# SCH_ESP-Mar_2024-04-21_1.net
KiCad netlist of a schematic drawn in EasyEDA
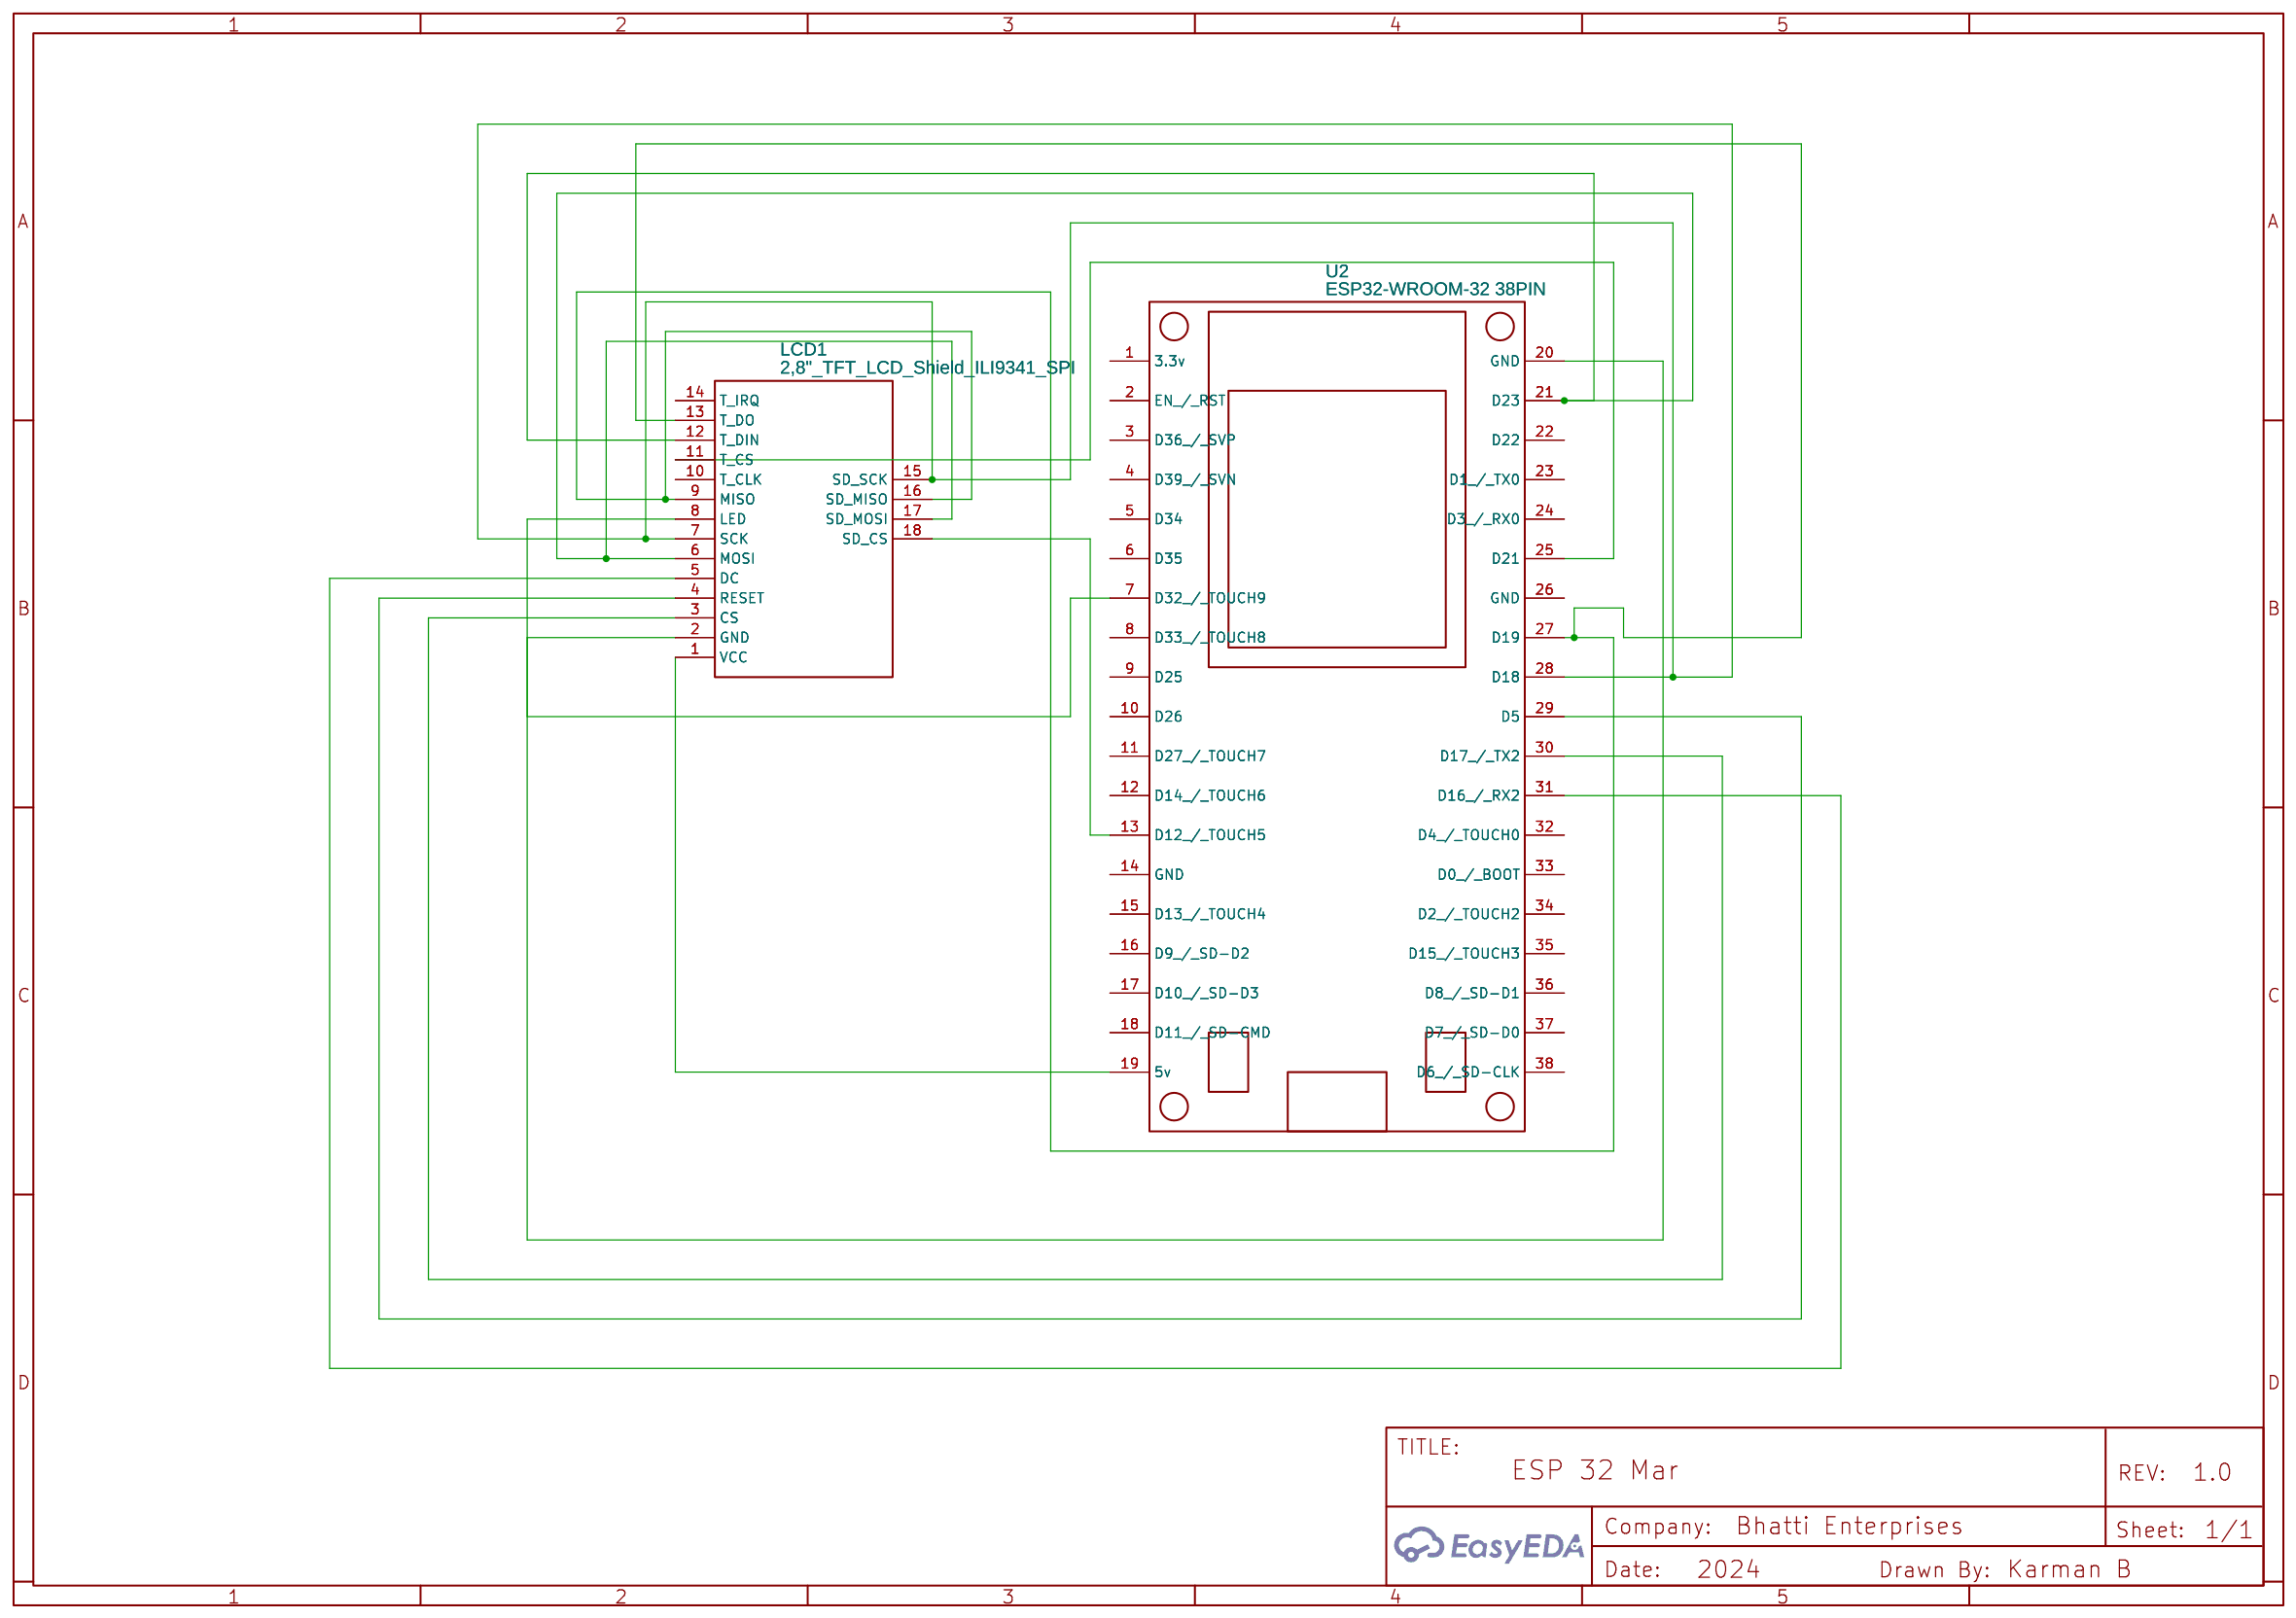
[diagram p0: Sheet_1]
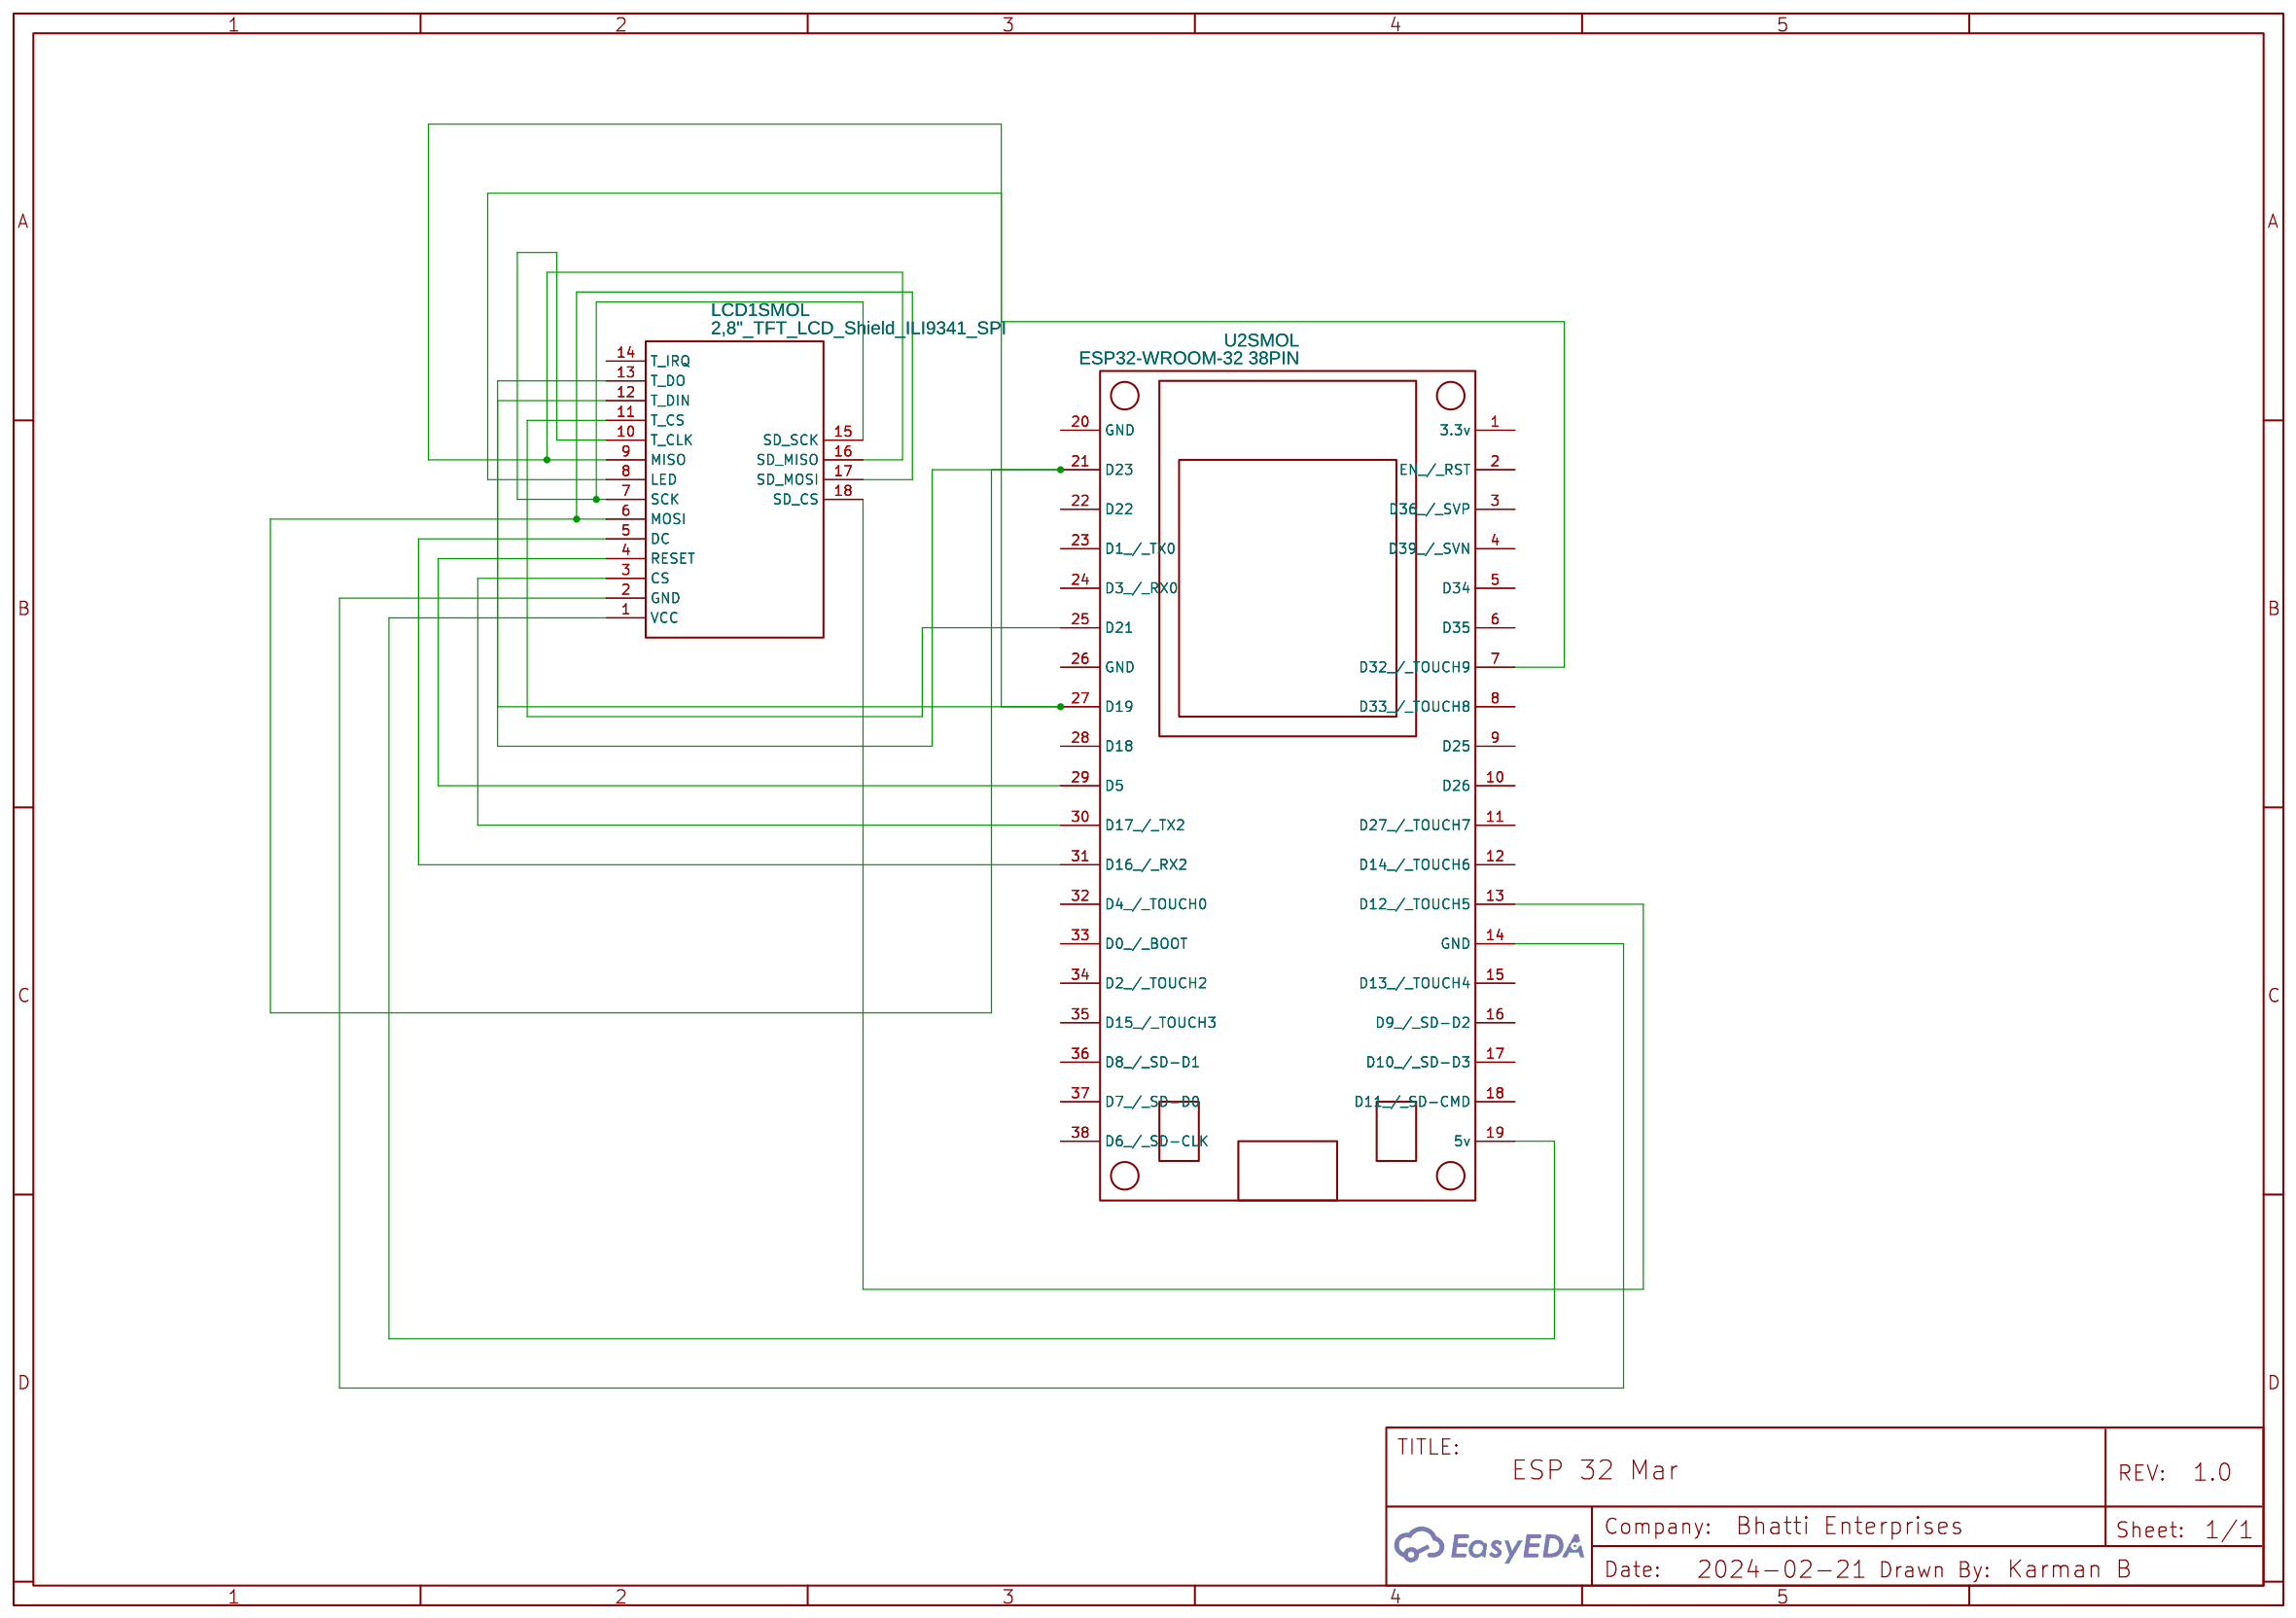
[diagram p1: Sheet SMOL]

(export (version "E")
  (design (tool "Eeschema 10.0.6"))
  (components
    (comp (ref "LCD1")
      (value "2,8\"_TFT_LCD_Shield_ILI9341_SPI")
      (libsource (lib "") (part "2,8{dblquote}_TFT_LCD_Shield_ILI9341_SPI"))
    )
    (comp (ref "U2")
      (value "ESP32-WROOM-32 38PIN")
      (fields (field (name "Manufacturer Part") "ESP32 Development Board"))
      (libsource (lib "") (part "ESP32-WROOM-32 38PIN"))
    )
    (comp (ref "LCD1SMOL")
      (value "2,8\"_TFT_LCD_Shield_ILI9341_SPI")
      (libsource (lib "") (part "2,8{dblquote}_TFT_LCD_Shield_ILI9341_SPI"))
    )
    (comp (ref "U2SMOL")
      (value "ESP32-WROOM-32 38PIN")
      (fields (field (name "Manufacturer Part") "ESP32 Development Board"))
      (libsource (lib "") (part "ESP32-WROOM-32 38PIN"))
    )
  )
  (nets
    (net (code "1") (name "Net-(LCD1-CS)") (class "Default")
      (node (ref "LCD1") (pin "3") (pinfunction "CS_3") (pintype "unspecified"))
      (node (ref "U2") (pin "30") (pinfunction "D17_/_TX2_30") (pintype "bidirectional"))
    )
    (net (code "2") (name "Net-(LCD1-DC)") (class "Default")
      (node (ref "LCD1") (pin "5") (pinfunction "DC_5") (pintype "unspecified"))
      (node (ref "U2") (pin "31") (pinfunction "D16_/_RX2_31") (pintype "bidirectional"))
    )
    (net (code "3") (name "Net-(LCD1-GND)") (class "Default")
      (node (ref "LCD1") (pin "2") (pinfunction "GND_2") (pintype "unspecified"))
      (node (ref "U2") (pin "20") (pinfunction "GND_20") (pintype "passive"))
    )
    (net (code "4") (name "Net-(LCD1-LED)") (class "Default")
      (node (ref "LCD1") (pin "8") (pinfunction "LED_8") (pintype "unspecified"))
      (node (ref "U2") (pin "7") (pinfunction "D32_/_TOUCH9_7") (pintype "bidirectional"))
    )
    (net (code "5") (name "Net-(LCD1-MISO)") (class "Default")
      (node (ref "LCD1") (pin "13") (pinfunction "T_DO_13") (pintype "unspecified"))
      (node (ref "LCD1") (pin "16") (pinfunction "SD_MISO_16") (pintype "unspecified"))
      (node (ref "LCD1") (pin "9") (pinfunction "MISO_9") (pintype "unspecified"))
      (node (ref "U2") (pin "27") (pinfunction "D19_27") (pintype "bidirectional"))
    )
    (net (code "6") (name "Net-(LCD1-MOSI)") (class "Default")
      (node (ref "LCD1") (pin "12") (pinfunction "T_DIN_12") (pintype "unspecified"))
      (node (ref "LCD1") (pin "17") (pinfunction "SD_MOSI_17") (pintype "unspecified"))
      (node (ref "LCD1") (pin "6") (pinfunction "MOSI_6") (pintype "unspecified"))
      (node (ref "U2") (pin "21") (pinfunction "D23_21") (pintype "bidirectional"))
    )
    (net (code "7") (name "Net-(LCD1-RESET)") (class "Default")
      (node (ref "LCD1") (pin "4") (pinfunction "RESET_4") (pintype "unspecified"))
      (node (ref "U2") (pin "29") (pinfunction "D5_29") (pintype "bidirectional"))
    )
    (net (code "8") (name "Net-(LCD1-SCK)") (class "Default")
      (node (ref "LCD1") (pin "15") (pinfunction "SD_SCK_15") (pintype "unspecified"))
      (node (ref "LCD1") (pin "7") (pinfunction "SCK_7") (pintype "unspecified"))
      (node (ref "U2") (pin "28") (pinfunction "D18_28") (pintype "bidirectional"))
    )
    (net (code "9") (name "Net-(LCD1-SD_CS)") (class "Default")
      (node (ref "LCD1") (pin "18") (pinfunction "SD_CS_18") (pintype "unspecified"))
      (node (ref "U2") (pin "13") (pinfunction "D12_/_TOUCH5_13") (pintype "bidirectional"))
    )
    (net (code "10") (name "Net-(LCD1-T_CS)") (class "Default")
      (node (ref "LCD1") (pin "11") (pinfunction "T_CS_11") (pintype "unspecified"))
      (node (ref "U2") (pin "25") (pinfunction "D21_25") (pintype "bidirectional"))
    )
    (net (code "11") (name "Net-(LCD1-VCC)") (class "Default")
      (node (ref "LCD1") (pin "1") (pinfunction "VCC_1") (pintype "unspecified"))
      (node (ref "U2") (pin "19") (pinfunction "5v_19") (pintype "passive"))
    )
    (net (code "12") (name "Net-(LCD1SMOL-CS)") (class "Default")
      (node (ref "LCD1SMOL") (pin "3") (pinfunction "CS_3") (pintype "unspecified"))
      (node (ref "U2SMOL") (pin "30") (pinfunction "D17_/_TX2_30") (pintype "bidirectional"))
    )
    (net (code "13") (name "Net-(LCD1SMOL-DC)") (class "Default")
      (node (ref "LCD1SMOL") (pin "5") (pinfunction "DC_5") (pintype "unspecified"))
      (node (ref "U2SMOL") (pin "31") (pinfunction "D16_/_RX2_31") (pintype "bidirectional"))
    )
    (net (code "14") (name "Net-(LCD1SMOL-GND)") (class "Default")
      (node (ref "LCD1SMOL") (pin "2") (pinfunction "GND_2") (pintype "unspecified"))
      (node (ref "U2SMOL") (pin "14") (pinfunction "GND_14") (pintype "passive"))
    )
    (net (code "15") (name "Net-(LCD1SMOL-LED)") (class "Default")
      (node (ref "LCD1SMOL") (pin "8") (pinfunction "LED_8") (pintype "unspecified"))
      (node (ref "U2SMOL") (pin "7") (pinfunction "D32_/_TOUCH9_7") (pintype "bidirectional"))
    )
    (net (code "16") (name "Net-(LCD1SMOL-MISO)") (class "Default")
      (node (ref "LCD1SMOL") (pin "13") (pinfunction "T_DO_13") (pintype "unspecified"))
      (node (ref "LCD1SMOL") (pin "16") (pinfunction "SD_MISO_16") (pintype "unspecified"))
      (node (ref "LCD1SMOL") (pin "9") (pinfunction "MISO_9") (pintype "unspecified"))
      (node (ref "U2SMOL") (pin "27") (pinfunction "D19_27") (pintype "bidirectional"))
    )
    (net (code "17") (name "Net-(LCD1SMOL-MOSI)") (class "Default")
      (node (ref "LCD1SMOL") (pin "12") (pinfunction "T_DIN_12") (pintype "unspecified"))
      (node (ref "LCD1SMOL") (pin "17") (pinfunction "SD_MOSI_17") (pintype "unspecified"))
      (node (ref "LCD1SMOL") (pin "6") (pinfunction "MOSI_6") (pintype "unspecified"))
      (node (ref "U2SMOL") (pin "21") (pinfunction "D23_21") (pintype "bidirectional"))
    )
    (net (code "18") (name "Net-(LCD1SMOL-RESET)") (class "Default")
      (node (ref "LCD1SMOL") (pin "4") (pinfunction "RESET_4") (pintype "unspecified"))
      (node (ref "U2SMOL") (pin "29") (pinfunction "D5_29") (pintype "bidirectional"))
    )
    (net (code "19") (name "Net-(LCD1SMOL-SCK)") (class "Default")
      (node (ref "LCD1SMOL") (pin "10") (pinfunction "T_CLK_10") (pintype "unspecified"))
      (node (ref "LCD1SMOL") (pin "15") (pinfunction "SD_SCK_15") (pintype "unspecified"))
      (node (ref "LCD1SMOL") (pin "7") (pinfunction "SCK_7") (pintype "unspecified"))
    )
    (net (code "20") (name "Net-(LCD1SMOL-SD_CS)") (class "Default")
      (node (ref "LCD1SMOL") (pin "18") (pinfunction "SD_CS_18") (pintype "unspecified"))
      (node (ref "U2SMOL") (pin "13") (pinfunction "D12_/_TOUCH5_13") (pintype "bidirectional"))
    )
    (net (code "21") (name "Net-(LCD1SMOL-T_CS)") (class "Default")
      (node (ref "LCD1SMOL") (pin "11") (pinfunction "T_CS_11") (pintype "unspecified"))
      (node (ref "U2SMOL") (pin "25") (pinfunction "D21_25") (pintype "bidirectional"))
    )
    (net (code "22") (name "Net-(LCD1SMOL-VCC)") (class "Default")
      (node (ref "LCD1SMOL") (pin "1") (pinfunction "VCC_1") (pintype "unspecified"))
      (node (ref "U2SMOL") (pin "19") (pinfunction "5v_19") (pintype "passive"))
    )
    (net (code "23") (name "unconnected-(LCD1-T_CLK-Pad10)") (class "Default")
      (node (ref "LCD1") (pin "10") (pinfunction "T_CLK_10") (pintype "unspecified"))
    )
    (net (code "24") (name "unconnected-(LCD1-T_IRQ-Pad14)") (class "Default")
      (node (ref "LCD1") (pin "14") (pinfunction "T_IRQ_14") (pintype "unspecified"))
    )
    (net (code "25") (name "unconnected-(LCD1SMOL-T_IRQ-Pad14)") (class "Default")
      (node (ref "LCD1SMOL") (pin "14") (pinfunction "T_IRQ_14") (pintype "unspecified"))
    )
    (net (code "26") (name "unconnected-(U2-3.3v-Pad1)") (class "Default")
      (node (ref "U2") (pin "1") (pinfunction "3.3v_1") (pintype "passive"))
    )
    (net (code "27") (name "unconnected-(U2-D0_{slash}_BOOT-Pad33)") (class "Default")
      (node (ref "U2") (pin "33") (pinfunction "D0_/_BOOT_33") (pintype "bidirectional"))
    )
    (net (code "28") (name "unconnected-(U2-D1_{slash}_TX0-Pad23)") (class "Default")
      (node (ref "U2") (pin "23") (pinfunction "D1_/_TX0_23") (pintype "bidirectional"))
    )
    (net (code "29") (name "unconnected-(U2-D2_{slash}_TOUCH2-Pad34)") (class "Default")
      (node (ref "U2") (pin "34") (pinfunction "D2_/_TOUCH2_34") (pintype "bidirectional"))
    )
    (net (code "30") (name "unconnected-(U2-D3_{slash}_RX0-Pad24)") (class "Default")
      (node (ref "U2") (pin "24") (pinfunction "D3_/_RX0_24") (pintype "bidirectional"))
    )
    (net (code "31") (name "unconnected-(U2-D4_{slash}_TOUCH0-Pad32)") (class "Default")
      (node (ref "U2") (pin "32") (pinfunction "D4_/_TOUCH0_32") (pintype "bidirectional"))
    )
    (net (code "32") (name "unconnected-(U2-D6_{slash}_SD-CLK-Pad38)") (class "Default")
      (node (ref "U2") (pin "38") (pinfunction "D6_/_SD-CLK_38") (pintype "bidirectional"))
    )
    (net (code "33") (name "unconnected-(U2-D7_{slash}_SD-D0-Pad37)") (class "Default")
      (node (ref "U2") (pin "37") (pinfunction "D7_/_SD-D0_37") (pintype "bidirectional"))
    )
    (net (code "34") (name "unconnected-(U2-D8_{slash}_SD-D1-Pad36)") (class "Default")
      (node (ref "U2") (pin "36") (pinfunction "D8_/_SD-D1_36") (pintype "bidirectional"))
    )
    (net (code "35") (name "unconnected-(U2-D9_{slash}_SD-D2-Pad16)") (class "Default")
      (node (ref "U2") (pin "16") (pinfunction "D9_/_SD-D2_16") (pintype "bidirectional"))
    )
    (net (code "36") (name "unconnected-(U2-D10_{slash}_SD-D3-Pad17)") (class "Default")
      (node (ref "U2") (pin "17") (pinfunction "D10_/_SD-D3_17") (pintype "bidirectional"))
    )
    (net (code "37") (name "unconnected-(U2-D11_{slash}_SD-CMD-Pad18)") (class "Default")
      (node (ref "U2") (pin "18") (pinfunction "D11_/_SD-CMD_18") (pintype "bidirectional"))
    )
    (net (code "38") (name "unconnected-(U2-D13_{slash}_TOUCH4-Pad15)") (class "Default")
      (node (ref "U2") (pin "15") (pinfunction "D13_/_TOUCH4_15") (pintype "bidirectional"))
    )
    (net (code "39") (name "unconnected-(U2-D14_{slash}_TOUCH6-Pad12)") (class "Default")
      (node (ref "U2") (pin "12") (pinfunction "D14_/_TOUCH6_12") (pintype "bidirectional"))
    )
    (net (code "40") (name "unconnected-(U2-D15_{slash}_TOUCH3-Pad35)") (class "Default")
      (node (ref "U2") (pin "35") (pinfunction "D15_/_TOUCH3_35") (pintype "bidirectional"))
    )
    (net (code "41") (name "unconnected-(U2-D22-Pad22)") (class "Default")
      (node (ref "U2") (pin "22") (pinfunction "D22_22") (pintype "bidirectional"))
    )
    (net (code "42") (name "unconnected-(U2-D25-Pad9)") (class "Default")
      (node (ref "U2") (pin "9") (pinfunction "D25_9") (pintype "bidirectional"))
    )
    (net (code "43") (name "unconnected-(U2-D26-Pad10)") (class "Default")
      (node (ref "U2") (pin "10") (pinfunction "D26_10") (pintype "bidirectional"))
    )
    (net (code "44") (name "unconnected-(U2-D27_{slash}_TOUCH7-Pad11)") (class "Default")
      (node (ref "U2") (pin "11") (pinfunction "D27_/_TOUCH7_11") (pintype "bidirectional"))
    )
    (net (code "45") (name "unconnected-(U2-D33_{slash}_TOUCH8-Pad8)") (class "Default")
      (node (ref "U2") (pin "8") (pinfunction "D33_/_TOUCH8_8") (pintype "bidirectional"))
    )
    (net (code "46") (name "unconnected-(U2-D34-Pad5)") (class "Default")
      (node (ref "U2") (pin "5") (pinfunction "D34_5") (pintype "bidirectional"))
    )
    (net (code "47") (name "unconnected-(U2-D35-Pad6)") (class "Default")
      (node (ref "U2") (pin "6") (pinfunction "D35_6") (pintype "bidirectional"))
    )
    (net (code "48") (name "unconnected-(U2-D36_{slash}_SVP-Pad3)") (class "Default")
      (node (ref "U2") (pin "3") (pinfunction "D36_/_SVP_3") (pintype "bidirectional"))
    )
    (net (code "49") (name "unconnected-(U2-D39_{slash}_SVN-Pad4)") (class "Default")
      (node (ref "U2") (pin "4") (pinfunction "D39_/_SVN_4") (pintype "bidirectional"))
    )
    (net (code "50") (name "unconnected-(U2-EN_{slash}_RST-Pad2)") (class "Default")
      (node (ref "U2") (pin "2") (pinfunction "EN_/_RST_2") (pintype "bidirectional"))
    )
    (net (code "51") (name "unconnected-(U2-GND-Pad14)") (class "Default")
      (node (ref "U2") (pin "14") (pinfunction "GND_14") (pintype "passive"))
    )
    (net (code "52") (name "unconnected-(U2-GND-Pad26)") (class "Default")
      (node (ref "U2") (pin "26") (pinfunction "GND_26") (pintype "passive"))
    )
    (net (code "53") (name "unconnected-(U2SMOL-3.3v-Pad1)") (class "Default")
      (node (ref "U2SMOL") (pin "1") (pinfunction "3.3v_1") (pintype "passive"))
    )
    (net (code "54") (name "unconnected-(U2SMOL-D0_{slash}_BOOT-Pad33)") (class "Default")
      (node (ref "U2SMOL") (pin "33") (pinfunction "D0_/_BOOT_33") (pintype "bidirectional"))
    )
    (net (code "55") (name "unconnected-(U2SMOL-D1_{slash}_TX0-Pad23)") (class "Default")
      (node (ref "U2SMOL") (pin "23") (pinfunction "D1_/_TX0_23") (pintype "bidirectional"))
    )
    (net (code "56") (name "unconnected-(U2SMOL-D2_{slash}_TOUCH2-Pad34)") (class "Default")
      (node (ref "U2SMOL") (pin "34") (pinfunction "D2_/_TOUCH2_34") (pintype "bidirectional"))
    )
    (net (code "57") (name "unconnected-(U2SMOL-D3_{slash}_RX0-Pad24)") (class "Default")
      (node (ref "U2SMOL") (pin "24") (pinfunction "D3_/_RX0_24") (pintype "bidirectional"))
    )
    (net (code "58") (name "unconnected-(U2SMOL-D4_{slash}_TOUCH0-Pad32)") (class "Default")
      (node (ref "U2SMOL") (pin "32") (pinfunction "D4_/_TOUCH0_32") (pintype "bidirectional"))
    )
    (net (code "59") (name "unconnected-(U2SMOL-D6_{slash}_SD-CLK-Pad38)") (class "Default")
      (node (ref "U2SMOL") (pin "38") (pinfunction "D6_/_SD-CLK_38") (pintype "bidirectional"))
    )
    (net (code "60") (name "unconnected-(U2SMOL-D7_{slash}_SD-D0-Pad37)") (class "Default")
      (node (ref "U2SMOL") (pin "37") (pinfunction "D7_/_SD-D0_37") (pintype "bidirectional"))
    )
    (net (code "61") (name "unconnected-(U2SMOL-D8_{slash}_SD-D1-Pad36)") (class "Default")
      (node (ref "U2SMOL") (pin "36") (pinfunction "D8_/_SD-D1_36") (pintype "bidirectional"))
    )
    (net (code "62") (name "unconnected-(U2SMOL-D9_{slash}_SD-D2-Pad16)") (class "Default")
      (node (ref "U2SMOL") (pin "16") (pinfunction "D9_/_SD-D2_16") (pintype "bidirectional"))
    )
    (net (code "63") (name "unconnected-(U2SMOL-D10_{slash}_SD-D3-Pad17)") (class "Default")
      (node (ref "U2SMOL") (pin "17") (pinfunction "D10_/_SD-D3_17") (pintype "bidirectional"))
    )
    (net (code "64") (name "unconnected-(U2SMOL-D11_{slash}_SD-CMD-Pad18)") (class "Default")
      (node (ref "U2SMOL") (pin "18") (pinfunction "D11_/_SD-CMD_18") (pintype "bidirectional"))
    )
    (net (code "65") (name "unconnected-(U2SMOL-D13_{slash}_TOUCH4-Pad15)") (class "Default")
      (node (ref "U2SMOL") (pin "15") (pinfunction "D13_/_TOUCH4_15") (pintype "bidirectional"))
    )
    (net (code "66") (name "unconnected-(U2SMOL-D14_{slash}_TOUCH6-Pad12)") (class "Default")
      (node (ref "U2SMOL") (pin "12") (pinfunction "D14_/_TOUCH6_12") (pintype "bidirectional"))
    )
    (net (code "67") (name "unconnected-(U2SMOL-D15_{slash}_TOUCH3-Pad35)") (class "Default")
      (node (ref "U2SMOL") (pin "35") (pinfunction "D15_/_TOUCH3_35") (pintype "bidirectional"))
    )
    (net (code "68") (name "unconnected-(U2SMOL-D18-Pad28)") (class "Default")
      (node (ref "U2SMOL") (pin "28") (pinfunction "D18_28") (pintype "bidirectional"))
    )
    (net (code "69") (name "unconnected-(U2SMOL-D22-Pad22)") (class "Default")
      (node (ref "U2SMOL") (pin "22") (pinfunction "D22_22") (pintype "bidirectional"))
    )
    (net (code "70") (name "unconnected-(U2SMOL-D25-Pad9)") (class "Default")
      (node (ref "U2SMOL") (pin "9") (pinfunction "D25_9") (pintype "bidirectional"))
    )
    (net (code "71") (name "unconnected-(U2SMOL-D26-Pad10)") (class "Default")
      (node (ref "U2SMOL") (pin "10") (pinfunction "D26_10") (pintype "bidirectional"))
    )
    (net (code "72") (name "unconnected-(U2SMOL-D27_{slash}_TOUCH7-Pad11)") (class "Default")
      (node (ref "U2SMOL") (pin "11") (pinfunction "D27_/_TOUCH7_11") (pintype "bidirectional"))
    )
    (net (code "73") (name "unconnected-(U2SMOL-D33_{slash}_TOUCH8-Pad8)") (class "Default")
      (node (ref "U2SMOL") (pin "8") (pinfunction "D33_/_TOUCH8_8") (pintype "bidirectional"))
    )
    (net (code "74") (name "unconnected-(U2SMOL-D34-Pad5)") (class "Default")
      (node (ref "U2SMOL") (pin "5") (pinfunction "D34_5") (pintype "bidirectional"))
    )
    (net (code "75") (name "unconnected-(U2SMOL-D35-Pad6)") (class "Default")
      (node (ref "U2SMOL") (pin "6") (pinfunction "D35_6") (pintype "bidirectional"))
    )
    (net (code "76") (name "unconnected-(U2SMOL-D36_{slash}_SVP-Pad3)") (class "Default")
      (node (ref "U2SMOL") (pin "3") (pinfunction "D36_/_SVP_3") (pintype "bidirectional"))
    )
    (net (code "77") (name "unconnected-(U2SMOL-D39_{slash}_SVN-Pad4)") (class "Default")
      (node (ref "U2SMOL") (pin "4") (pinfunction "D39_/_SVN_4") (pintype "bidirectional"))
    )
    (net (code "78") (name "unconnected-(U2SMOL-EN_{slash}_RST-Pad2)") (class "Default")
      (node (ref "U2SMOL") (pin "2") (pinfunction "EN_/_RST_2") (pintype "bidirectional"))
    )
    (net (code "79") (name "unconnected-(U2SMOL-GND-Pad20)") (class "Default")
      (node (ref "U2SMOL") (pin "20") (pinfunction "GND_20") (pintype "passive"))
    )
    (net (code "80") (name "unconnected-(U2SMOL-GND-Pad26)") (class "Default")
      (node (ref "U2SMOL") (pin "26") (pinfunction "GND_26") (pintype "passive"))
    )
  )
)
